# BMP388.net
KiCad netlist of a schematic drawn in Altium Designer
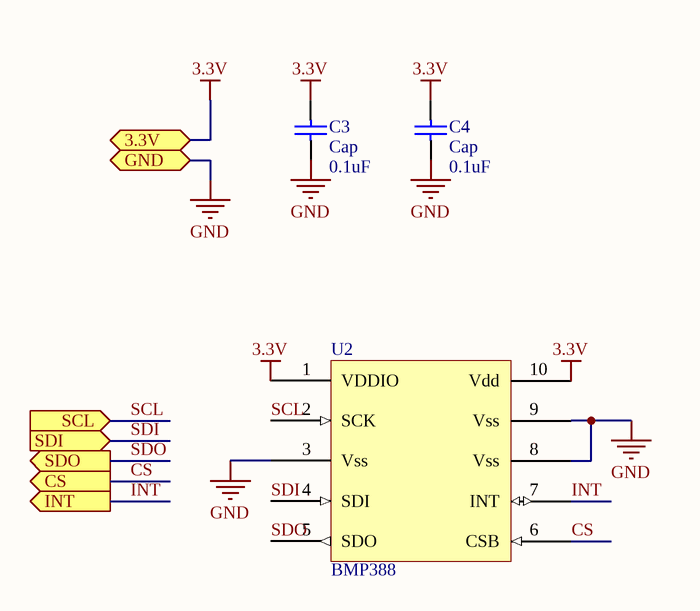
[diagram p0: BMP388.SchDoc]

(export (version "E")
  (design (tool "Eeschema 10.0.6"))
  (components
    (comp (ref "C3")
      (value "Cap")
      (footprint "0603")
      (description "Capacitor")
      (fields (field (name "ALTIUM_VALUE") "0.1uF") (field (name "PUBLISHER") "Altium Limited"))
      (libsource (lib "Miscellaneous Devices") (part "Cap"))
    )
    (comp (ref "C4")
      (value "Cap")
      (footprint "0603")
      (description "Capacitor")
      (fields (field (name "ALTIUM_VALUE") "0.1uF") (field (name "PUBLISHER") "Altium Limited"))
      (libsource (lib "Miscellaneous Devices") (part "Cap"))
    )
    (comp (ref "U2") (value "BMP388") (footprint "BMP388") (libsource (lib "SchlibSensors") (part "BMP388")))
  )
  (nets
    (net (code "1") (name "/CS") (class "Default")
      (node (ref "U2") (pin "6") (pinfunction "CSB_6") (pintype "input"))
    )
    (net (code "2") (name "/INT") (class "Default")
      (node (ref "U2") (pin "7") (pinfunction "INT_7") (pintype "bidirectional"))
    )
    (net (code "3") (name "/SCL") (class "Default")
      (node (ref "U2") (pin "2") (pinfunction "SCK_2") (pintype "input"))
    )
    (net (code "4") (name "/SDI") (class "Default")
      (node (ref "U2") (pin "4") (pinfunction "SDI_4") (pintype "input"))
    )
    (net (code "5") (name "/SDO") (class "Default")
      (node (ref "U2") (pin "5") (pinfunction "SDO_5") (pintype "output"))
    )
    (net (code "6") (name "3.3V") (class "Default")
      (node (ref "C3") (pin "1") (pinfunction "1_1") (pintype "passive"))
      (node (ref "C4") (pin "1") (pinfunction "1_1") (pintype "passive"))
      (node (ref "U2") (pin "1") (pinfunction "VDDIO_1") (pintype "power_in"))
      (node (ref "U2") (pin "10") (pinfunction "Vdd_10") (pintype "power_in"))
    )
    (net (code "7") (name "GND") (class "Default")
      (node (ref "C3") (pin "2") (pinfunction "2_2") (pintype "passive"))
      (node (ref "C4") (pin "2") (pinfunction "2_2") (pintype "passive"))
      (node (ref "U2") (pin "3") (pinfunction "Vss_3") (pintype "power_in"))
      (node (ref "U2") (pin "8") (pinfunction "Vss_8") (pintype "power_in"))
      (node (ref "U2") (pin "9") (pinfunction "Vss_9") (pintype "power_in"))
    )
  )
)
